# Sample.net
KiCad netlist of a schematic drawn in EAGLE
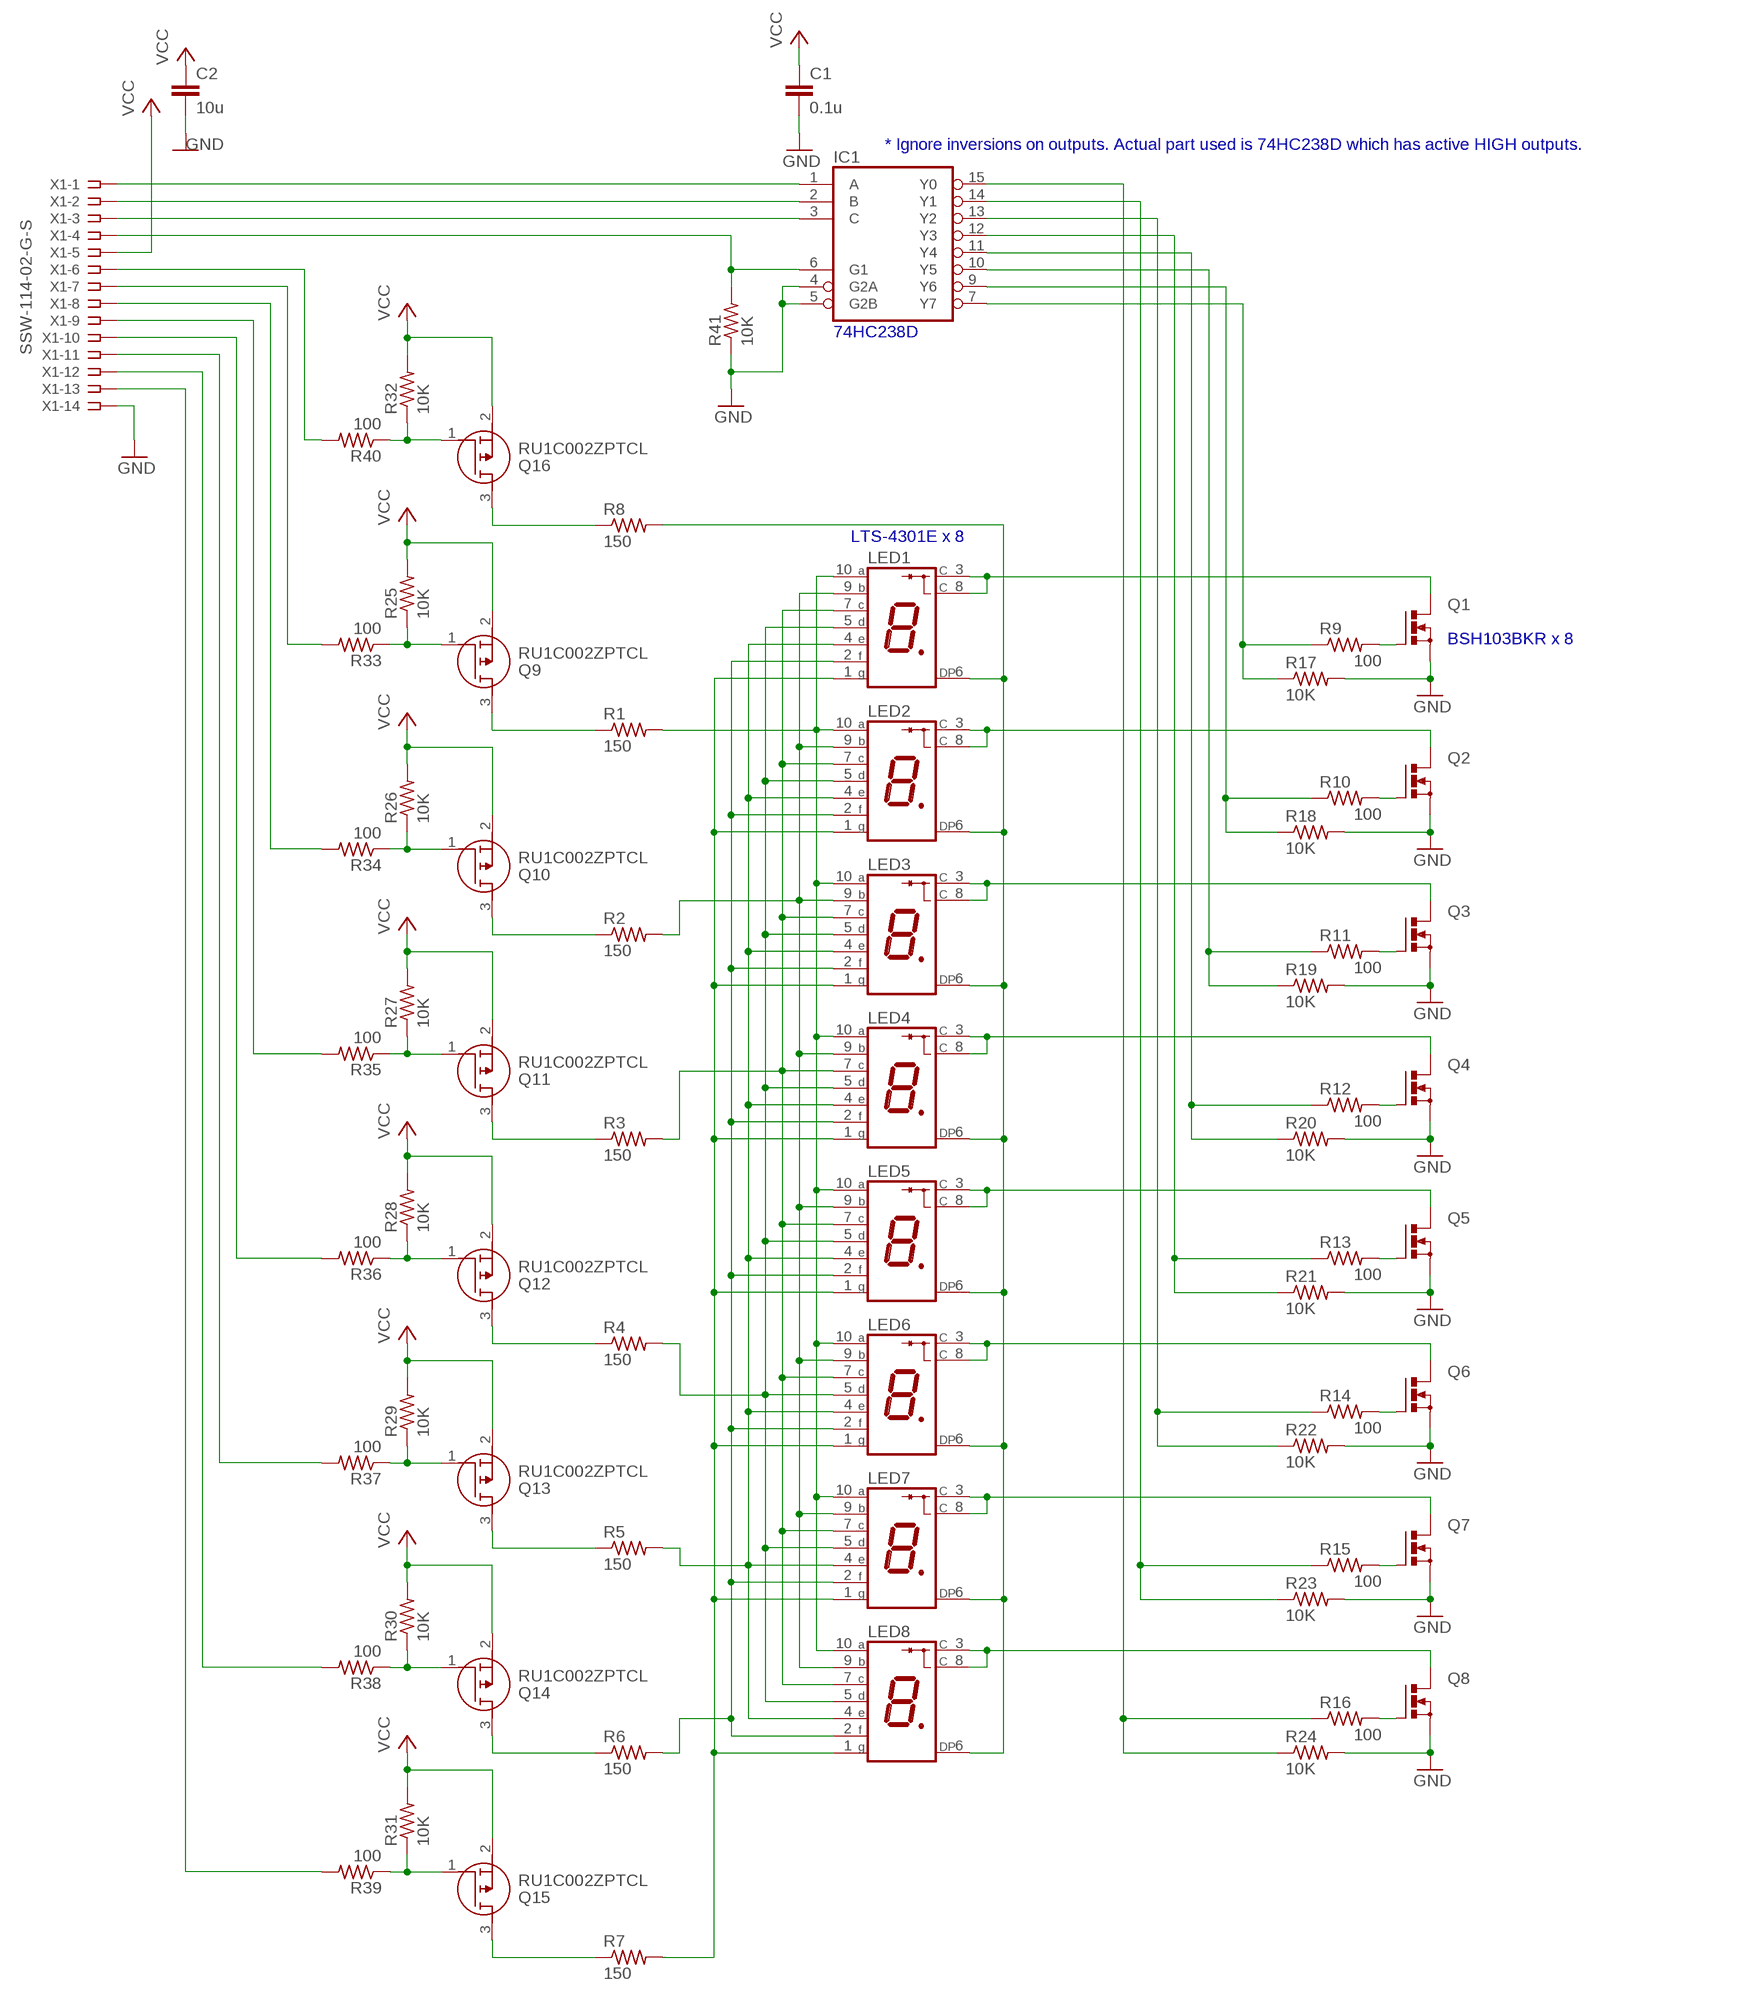
[diagram p0: schematic, sheet 1]

(export (version "E")
  (design (tool "Eeschema 10.0.6"))
  (components
    (comp (ref "C1")
      (value "0.1u")
      (footprint "eagle-import:C0805")
      (libsource (lib "eagle-import") (part "C-EUC0805"))
    )
    (comp (ref "C2")
      (value "10u")
      (footprint "eagle-import:C0805")
      (libsource (lib "eagle-import") (part "C-EUC0805"))
    )
    (comp (ref "IC1")
      (value "74S138D")
      (footprint "eagle-import:SO16")
      (libsource (lib "eagle-import") (part "74138DS"))
    )
    (comp (ref "LED1")
      (value "S4301B")
      (footprint "eagle-import:S4301B")
      (libsource (lib "eagle-import") (part "S4301B"))
    )
    (comp (ref "LED2")
      (value "S4301B")
      (footprint "eagle-import:S4301B")
      (libsource (lib "eagle-import") (part "S4301B"))
    )
    (comp (ref "LED3")
      (value "S4301B")
      (footprint "eagle-import:S4301B")
      (libsource (lib "eagle-import") (part "S4301B"))
    )
    (comp (ref "LED4")
      (value "S4301B")
      (footprint "eagle-import:S4301B")
      (libsource (lib "eagle-import") (part "S4301B"))
    )
    (comp (ref "LED5")
      (value "S4301B")
      (footprint "eagle-import:S4301B")
      (libsource (lib "eagle-import") (part "S4301B"))
    )
    (comp (ref "LED6")
      (value "S4301B")
      (footprint "eagle-import:S4301B")
      (libsource (lib "eagle-import") (part "S4301B"))
    )
    (comp (ref "LED7")
      (value "S4301B")
      (footprint "eagle-import:S4301B")
      (libsource (lib "eagle-import") (part "S4301B"))
    )
    (comp (ref "LED8")
      (value "S4301B")
      (footprint "eagle-import:S4301B")
      (libsource (lib "eagle-import") (part "S4301B"))
    )
    (comp (ref "Q1")
      (value "N-MOSFET-SO8")
      (footprint "eagle-import:SUPER-SOT3")
      (libsource (lib "eagle-import") (part "N-MOSFET-SO8"))
    )
    (comp (ref "Q2")
      (value "N-MOSFET-SO8")
      (footprint "eagle-import:SUPER-SOT3")
      (libsource (lib "eagle-import") (part "N-MOSFET-SO8"))
    )
    (comp (ref "Q3")
      (value "N-MOSFET-SO8")
      (footprint "eagle-import:SUPER-SOT3")
      (libsource (lib "eagle-import") (part "N-MOSFET-SO8"))
    )
    (comp (ref "Q4")
      (value "N-MOSFET-SO8")
      (footprint "eagle-import:SUPER-SOT3")
      (libsource (lib "eagle-import") (part "N-MOSFET-SO8"))
    )
    (comp (ref "Q5")
      (value "N-MOSFET-SO8")
      (footprint "eagle-import:SUPER-SOT3")
      (libsource (lib "eagle-import") (part "N-MOSFET-SO8"))
    )
    (comp (ref "Q6")
      (value "N-MOSFET-SO8")
      (footprint "eagle-import:SUPER-SOT3")
      (libsource (lib "eagle-import") (part "N-MOSFET-SO8"))
    )
    (comp (ref "Q7")
      (value "N-MOSFET-SO8")
      (footprint "eagle-import:SUPER-SOT3")
      (libsource (lib "eagle-import") (part "N-MOSFET-SO8"))
    )
    (comp (ref "Q8")
      (value "N-MOSFET-SO8")
      (footprint "eagle-import:SUPER-SOT3")
      (libsource (lib "eagle-import") (part "N-MOSFET-SO8"))
    )
    (comp (ref "Q9")
      (value "RU1C002ZPTCL")
      (footprint "eagle-import:SOTFL65P210X105-3N")
      (fields (field (name "MOUSER_PART_NUMBER") "755-RU1C002ZPTCL"))
      (libsource (lib "eagle-import") (part "RU1C002ZPTCL"))
    )
    (comp (ref "Q10")
      (value "RU1C002ZPTCL")
      (footprint "eagle-import:SOTFL65P210X105-3N")
      (fields (field (name "MOUSER_PART_NUMBER") "755-RU1C002ZPTCL"))
      (libsource (lib "eagle-import") (part "RU1C002ZPTCL"))
    )
    (comp (ref "Q11")
      (value "RU1C002ZPTCL")
      (footprint "eagle-import:SOTFL65P210X105-3N")
      (fields (field (name "MOUSER_PART_NUMBER") "755-RU1C002ZPTCL"))
      (libsource (lib "eagle-import") (part "RU1C002ZPTCL"))
    )
    (comp (ref "Q12")
      (value "RU1C002ZPTCL")
      (footprint "eagle-import:SOTFL65P210X105-3N")
      (fields (field (name "MOUSER_PART_NUMBER") "755-RU1C002ZPTCL"))
      (libsource (lib "eagle-import") (part "RU1C002ZPTCL"))
    )
    (comp (ref "Q13")
      (value "RU1C002ZPTCL")
      (footprint "eagle-import:SOTFL65P210X105-3N")
      (fields (field (name "MOUSER_PART_NUMBER") "755-RU1C002ZPTCL"))
      (libsource (lib "eagle-import") (part "RU1C002ZPTCL"))
    )
    (comp (ref "Q14")
      (value "RU1C002ZPTCL")
      (footprint "eagle-import:SOTFL65P210X105-3N")
      (fields (field (name "MOUSER_PART_NUMBER") "755-RU1C002ZPTCL"))
      (libsource (lib "eagle-import") (part "RU1C002ZPTCL"))
    )
    (comp (ref "Q15")
      (value "RU1C002ZPTCL")
      (footprint "eagle-import:SOTFL65P210X105-3N")
      (fields (field (name "MOUSER_PART_NUMBER") "755-RU1C002ZPTCL"))
      (libsource (lib "eagle-import") (part "RU1C002ZPTCL"))
    )
    (comp (ref "Q16")
      (value "RU1C002ZPTCL")
      (footprint "eagle-import:SOTFL65P210X105-3N")
      (fields (field (name "MOUSER_PART_NUMBER") "755-RU1C002ZPTCL"))
      (libsource (lib "eagle-import") (part "RU1C002ZPTCL"))
    )
    (comp (ref "R1")
      (value "150")
      (footprint "eagle-import:R0805")
      (libsource (lib "eagle-import") (part "R-US_R0805"))
    )
    (comp (ref "R2")
      (value "150")
      (footprint "eagle-import:R0805")
      (libsource (lib "eagle-import") (part "R-US_R0805"))
    )
    (comp (ref "R3")
      (value "150")
      (footprint "eagle-import:R0805")
      (libsource (lib "eagle-import") (part "R-US_R0805"))
    )
    (comp (ref "R4")
      (value "150")
      (footprint "eagle-import:R0805")
      (libsource (lib "eagle-import") (part "R-US_R0805"))
    )
    (comp (ref "R5")
      (value "150")
      (footprint "eagle-import:R0805")
      (libsource (lib "eagle-import") (part "R-US_R0805"))
    )
    (comp (ref "R6")
      (value "150")
      (footprint "eagle-import:R0805")
      (libsource (lib "eagle-import") (part "R-US_R0805"))
    )
    (comp (ref "R7")
      (value "150")
      (footprint "eagle-import:R0805")
      (libsource (lib "eagle-import") (part "R-US_R0805"))
    )
    (comp (ref "R8")
      (value "150")
      (footprint "eagle-import:R0805")
      (libsource (lib "eagle-import") (part "R-US_R0805"))
    )
    (comp (ref "R9")
      (value "100")
      (footprint "eagle-import:R0805")
      (libsource (lib "eagle-import") (part "R-US_R0805"))
    )
    (comp (ref "R10")
      (value "100")
      (footprint "eagle-import:R0805")
      (libsource (lib "eagle-import") (part "R-US_R0805"))
    )
    (comp (ref "R11")
      (value "100")
      (footprint "eagle-import:R0805")
      (libsource (lib "eagle-import") (part "R-US_R0805"))
    )
    (comp (ref "R12")
      (value "100")
      (footprint "eagle-import:R0805")
      (libsource (lib "eagle-import") (part "R-US_R0805"))
    )
    (comp (ref "R13")
      (value "100")
      (footprint "eagle-import:R0805")
      (libsource (lib "eagle-import") (part "R-US_R0805"))
    )
    (comp (ref "R14")
      (value "100")
      (footprint "eagle-import:R0805")
      (libsource (lib "eagle-import") (part "R-US_R0805"))
    )
    (comp (ref "R15")
      (value "100")
      (footprint "eagle-import:R0805")
      (libsource (lib "eagle-import") (part "R-US_R0805"))
    )
    (comp (ref "R16")
      (value "100")
      (footprint "eagle-import:R0805")
      (libsource (lib "eagle-import") (part "R-US_R0805"))
    )
    (comp (ref "R17")
      (value "10K")
      (footprint "eagle-import:R0805")
      (libsource (lib "eagle-import") (part "R-US_R0805"))
    )
    (comp (ref "R18")
      (value "10K")
      (footprint "eagle-import:R0805")
      (libsource (lib "eagle-import") (part "R-US_R0805"))
    )
    (comp (ref "R19")
      (value "10K")
      (footprint "eagle-import:R0805")
      (libsource (lib "eagle-import") (part "R-US_R0805"))
    )
    (comp (ref "R20")
      (value "10K")
      (footprint "eagle-import:R0805")
      (libsource (lib "eagle-import") (part "R-US_R0805"))
    )
    (comp (ref "R21")
      (value "10K")
      (footprint "eagle-import:R0805")
      (libsource (lib "eagle-import") (part "R-US_R0805"))
    )
    (comp (ref "R22")
      (value "10K")
      (footprint "eagle-import:R0805")
      (libsource (lib "eagle-import") (part "R-US_R0805"))
    )
    (comp (ref "R23")
      (value "10K")
      (footprint "eagle-import:R0805")
      (libsource (lib "eagle-import") (part "R-US_R0805"))
    )
    (comp (ref "R24")
      (value "10K")
      (footprint "eagle-import:R0805")
      (libsource (lib "eagle-import") (part "R-US_R0805"))
    )
    (comp (ref "R25")
      (value "10K")
      (footprint "eagle-import:R0805")
      (libsource (lib "eagle-import") (part "R-US_R0805"))
    )
    (comp (ref "R26")
      (value "10K")
      (footprint "eagle-import:R0805")
      (libsource (lib "eagle-import") (part "R-US_R0805"))
    )
    (comp (ref "R27")
      (value "10K")
      (footprint "eagle-import:R0805")
      (libsource (lib "eagle-import") (part "R-US_R0805"))
    )
    (comp (ref "R28")
      (value "10K")
      (footprint "eagle-import:R0805")
      (libsource (lib "eagle-import") (part "R-US_R0805"))
    )
    (comp (ref "R29")
      (value "10K")
      (footprint "eagle-import:R0805")
      (libsource (lib "eagle-import") (part "R-US_R0805"))
    )
    (comp (ref "R30")
      (value "10K")
      (footprint "eagle-import:R0805")
      (libsource (lib "eagle-import") (part "R-US_R0805"))
    )
    (comp (ref "R31")
      (value "10K")
      (footprint "eagle-import:R0805")
      (libsource (lib "eagle-import") (part "R-US_R0805"))
    )
    (comp (ref "R32")
      (value "10K")
      (footprint "eagle-import:R0805")
      (libsource (lib "eagle-import") (part "R-US_R0805"))
    )
    (comp (ref "R33")
      (value "100")
      (footprint "eagle-import:R0805")
      (libsource (lib "eagle-import") (part "R-US_R0805"))
    )
    (comp (ref "R34")
      (value "100")
      (footprint "eagle-import:R0805")
      (libsource (lib "eagle-import") (part "R-US_R0805"))
    )
    (comp (ref "R35")
      (value "100")
      (footprint "eagle-import:R0805")
      (libsource (lib "eagle-import") (part "R-US_R0805"))
    )
    (comp (ref "R36")
      (value "100")
      (footprint "eagle-import:R0805")
      (libsource (lib "eagle-import") (part "R-US_R0805"))
    )
    (comp (ref "R37")
      (value "100")
      (footprint "eagle-import:R0805")
      (libsource (lib "eagle-import") (part "R-US_R0805"))
    )
    (comp (ref "R38")
      (value "100")
      (footprint "eagle-import:R0805")
      (libsource (lib "eagle-import") (part "R-US_R0805"))
    )
    (comp (ref "R39")
      (value "100")
      (footprint "eagle-import:R0805")
      (libsource (lib "eagle-import") (part "R-US_R0805"))
    )
    (comp (ref "R40")
      (value "100")
      (footprint "eagle-import:R0805")
      (libsource (lib "eagle-import") (part "R-US_R0805"))
    )
    (comp (ref "R41")
      (value "10K")
      (footprint "eagle-import:R0805")
      (libsource (lib "eagle-import") (part "R-US_R0805"))
    )
    (comp (ref "X1")
      (value "SSW-114-02-G-S")
      (footprint "eagle-import:SSW-114-02-G-S")
      (fields (field (name "MF") "Samtec Inc."))
      (libsource (lib "eagle-import") (part "SSW-114-02-G-S"))
    )
  )
  (nets
    (net (code "1") (name "GND") (class "Default")
      (node (ref "C1") (pin "2") (pinfunction "2_2") (pintype "passive"))
      (node (ref "C2") (pin "2") (pinfunction "2_2") (pintype "passive"))
      (node (ref "IC1") (pin "4") (pinfunction "G2A_4") (pintype "input"))
      (node (ref "IC1") (pin "5") (pinfunction "G2B_5") (pintype "input"))
      (node (ref "Q1") (pin "2") (pinfunction "S_2") (pintype "passive"))
      (node (ref "Q2") (pin "2") (pinfunction "S_2") (pintype "passive"))
      (node (ref "Q3") (pin "2") (pinfunction "S_2") (pintype "passive"))
      (node (ref "Q4") (pin "2") (pinfunction "S_2") (pintype "passive"))
      (node (ref "Q5") (pin "2") (pinfunction "S_2") (pintype "passive"))
      (node (ref "Q6") (pin "2") (pinfunction "S_2") (pintype "passive"))
      (node (ref "Q7") (pin "2") (pinfunction "S_2") (pintype "passive"))
      (node (ref "Q8") (pin "2") (pinfunction "S_2") (pintype "passive"))
      (node (ref "R17") (pin "2") (pinfunction "2_2") (pintype "passive"))
      (node (ref "R18") (pin "2") (pinfunction "2_2") (pintype "passive"))
      (node (ref "R19") (pin "2") (pinfunction "2_2") (pintype "passive"))
      (node (ref "R20") (pin "2") (pinfunction "2_2") (pintype "passive"))
      (node (ref "R21") (pin "2") (pinfunction "2_2") (pintype "passive"))
      (node (ref "R22") (pin "2") (pinfunction "2_2") (pintype "passive"))
      (node (ref "R23") (pin "2") (pinfunction "2_2") (pintype "passive"))
      (node (ref "R24") (pin "2") (pinfunction "2_2") (pintype "passive"))
      (node (ref "R41") (pin "1") (pinfunction "1_1") (pintype "passive"))
      (node (ref "X1") (pin "14") (pinfunction "1_14") (pintype "passive"))
    )
    (net (code "2") (name "Net-(IC1A-A)") (class "Default")
      (node (ref "IC1") (pin "1") (pinfunction "A_1") (pintype "input"))
      (node (ref "X1") (pin "1") (pinfunction "1_1") (pintype "passive"))
    )
    (net (code "3") (name "Net-(IC1A-B)") (class "Default")
      (node (ref "IC1") (pin "2") (pinfunction "B_2") (pintype "input"))
      (node (ref "X1") (pin "2") (pinfunction "1_2") (pintype "passive"))
    )
    (net (code "4") (name "Net-(IC1A-C)") (class "Default")
      (node (ref "IC1") (pin "3") (pinfunction "C_3") (pintype "input"))
      (node (ref "X1") (pin "3") (pinfunction "1_3") (pintype "passive"))
    )
    (net (code "5") (name "Net-(IC1A-G1)") (class "Default")
      (node (ref "IC1") (pin "6") (pinfunction "G1_6") (pintype "input"))
      (node (ref "R41") (pin "2") (pinfunction "2_2") (pintype "passive"))
      (node (ref "X1") (pin "4") (pinfunction "1_4") (pintype "passive"))
    )
    (net (code "6") (name "Net-(IC1A-Y0)") (class "Default")
      (node (ref "IC1") (pin "15") (pinfunction "Y0_15") (pintype "output"))
      (node (ref "R16") (pin "1") (pinfunction "1_1") (pintype "passive"))
      (node (ref "R24") (pin "1") (pinfunction "1_1") (pintype "passive"))
    )
    (net (code "7") (name "Net-(IC1A-Y1)") (class "Default")
      (node (ref "IC1") (pin "14") (pinfunction "Y1_14") (pintype "output"))
      (node (ref "R15") (pin "1") (pinfunction "1_1") (pintype "passive"))
      (node (ref "R23") (pin "1") (pinfunction "1_1") (pintype "passive"))
    )
    (net (code "8") (name "Net-(IC1A-Y2)") (class "Default")
      (node (ref "IC1") (pin "13") (pinfunction "Y2_13") (pintype "output"))
      (node (ref "R14") (pin "1") (pinfunction "1_1") (pintype "passive"))
      (node (ref "R22") (pin "1") (pinfunction "1_1") (pintype "passive"))
    )
    (net (code "9") (name "Net-(IC1A-Y3)") (class "Default")
      (node (ref "IC1") (pin "12") (pinfunction "Y3_12") (pintype "output"))
      (node (ref "R13") (pin "1") (pinfunction "1_1") (pintype "passive"))
      (node (ref "R21") (pin "1") (pinfunction "1_1") (pintype "passive"))
    )
    (net (code "10") (name "Net-(IC1A-Y4)") (class "Default")
      (node (ref "IC1") (pin "11") (pinfunction "Y4_11") (pintype "output"))
      (node (ref "R12") (pin "1") (pinfunction "1_1") (pintype "passive"))
      (node (ref "R20") (pin "1") (pinfunction "1_1") (pintype "passive"))
    )
    (net (code "11") (name "Net-(IC1A-Y5)") (class "Default")
      (node (ref "IC1") (pin "10") (pinfunction "Y5_10") (pintype "output"))
      (node (ref "R11") (pin "1") (pinfunction "1_1") (pintype "passive"))
      (node (ref "R19") (pin "1") (pinfunction "1_1") (pintype "passive"))
    )
    (net (code "12") (name "Net-(IC1A-Y6)") (class "Default")
      (node (ref "IC1") (pin "9") (pinfunction "Y6_9") (pintype "output"))
      (node (ref "R10") (pin "1") (pinfunction "1_1") (pintype "passive"))
      (node (ref "R18") (pin "1") (pinfunction "1_1") (pintype "passive"))
    )
    (net (code "13") (name "Net-(IC1A-Y7)") (class "Default")
      (node (ref "IC1") (pin "7") (pinfunction "Y7_7") (pintype "output"))
      (node (ref "R17") (pin "1") (pinfunction "1_1") (pintype "passive"))
      (node (ref "R9") (pin "1") (pinfunction "1_1") (pintype "passive"))
    )
    (net (code "14") (name "Net-(LED1-A)") (class "Default")
      (node (ref "LED1") (pin "10") (pinfunction "A_10") (pintype "passive"))
      (node (ref "LED2") (pin "10") (pinfunction "A_10") (pintype "passive"))
      (node (ref "LED3") (pin "10") (pinfunction "A_10") (pintype "passive"))
      (node (ref "LED4") (pin "10") (pinfunction "A_10") (pintype "passive"))
      (node (ref "LED5") (pin "10") (pinfunction "A_10") (pintype "passive"))
      (node (ref "LED6") (pin "10") (pinfunction "A_10") (pintype "passive"))
      (node (ref "LED7") (pin "10") (pinfunction "A_10") (pintype "passive"))
      (node (ref "LED8") (pin "10") (pinfunction "A_10") (pintype "passive"))
      (node (ref "R1") (pin "2") (pinfunction "2_2") (pintype "passive"))
    )
    (net (code "15") (name "Net-(LED1-B)") (class "Default")
      (node (ref "LED1") (pin "9") (pinfunction "B_9") (pintype "passive"))
      (node (ref "LED2") (pin "9") (pinfunction "B_9") (pintype "passive"))
      (node (ref "LED3") (pin "9") (pinfunction "B_9") (pintype "passive"))
      (node (ref "LED4") (pin "9") (pinfunction "B_9") (pintype "passive"))
      (node (ref "LED5") (pin "9") (pinfunction "B_9") (pintype "passive"))
      (node (ref "LED6") (pin "9") (pinfunction "B_9") (pintype "passive"))
      (node (ref "LED7") (pin "9") (pinfunction "B_9") (pintype "passive"))
      (node (ref "LED8") (pin "9") (pinfunction "B_9") (pintype "passive"))
      (node (ref "R2") (pin "2") (pinfunction "2_2") (pintype "passive"))
    )
    (net (code "16") (name "Net-(LED1-C-Pad7)") (class "Default")
      (node (ref "LED1") (pin "7") (pinfunction "C_7") (pintype "passive"))
      (node (ref "LED2") (pin "7") (pinfunction "C_7") (pintype "passive"))
      (node (ref "LED3") (pin "7") (pinfunction "C_7") (pintype "passive"))
      (node (ref "LED4") (pin "7") (pinfunction "C_7") (pintype "passive"))
      (node (ref "LED5") (pin "7") (pinfunction "C_7") (pintype "passive"))
      (node (ref "LED6") (pin "7") (pinfunction "C_7") (pintype "passive"))
      (node (ref "LED7") (pin "7") (pinfunction "C_7") (pintype "passive"))
      (node (ref "LED8") (pin "7") (pinfunction "C_7") (pintype "passive"))
      (node (ref "R3") (pin "2") (pinfunction "2_2") (pintype "passive"))
    )
    (net (code "17") (name "Net-(LED1-D)") (class "Default")
      (node (ref "LED1") (pin "5") (pinfunction "D_5") (pintype "passive"))
      (node (ref "LED2") (pin "5") (pinfunction "D_5") (pintype "passive"))
      (node (ref "LED3") (pin "5") (pinfunction "D_5") (pintype "passive"))
      (node (ref "LED4") (pin "5") (pinfunction "D_5") (pintype "passive"))
      (node (ref "LED5") (pin "5") (pinfunction "D_5") (pintype "passive"))
      (node (ref "LED6") (pin "5") (pinfunction "D_5") (pintype "passive"))
      (node (ref "LED7") (pin "5") (pinfunction "D_5") (pintype "passive"))
      (node (ref "LED8") (pin "5") (pinfunction "D_5") (pintype "passive"))
      (node (ref "R4") (pin "2") (pinfunction "2_2") (pintype "passive"))
    )
    (net (code "18") (name "Net-(LED1-DP)") (class "Default")
      (node (ref "LED1") (pin "6") (pinfunction "DP_6") (pintype "passive"))
      (node (ref "LED2") (pin "6") (pinfunction "DP_6") (pintype "passive"))
      (node (ref "LED3") (pin "6") (pinfunction "DP_6") (pintype "passive"))
      (node (ref "LED4") (pin "6") (pinfunction "DP_6") (pintype "passive"))
      (node (ref "LED5") (pin "6") (pinfunction "DP_6") (pintype "passive"))
      (node (ref "LED6") (pin "6") (pinfunction "DP_6") (pintype "passive"))
      (node (ref "LED7") (pin "6") (pinfunction "DP_6") (pintype "passive"))
      (node (ref "LED8") (pin "6") (pinfunction "DP_6") (pintype "passive"))
      (node (ref "R8") (pin "2") (pinfunction "2_2") (pintype "passive"))
    )
    (net (code "19") (name "Net-(LED1-E)") (class "Default")
      (node (ref "LED1") (pin "4") (pinfunction "E_4") (pintype "passive"))
      (node (ref "LED2") (pin "4") (pinfunction "E_4") (pintype "passive"))
      (node (ref "LED3") (pin "4") (pinfunction "E_4") (pintype "passive"))
      (node (ref "LED4") (pin "4") (pinfunction "E_4") (pintype "passive"))
      (node (ref "LED5") (pin "4") (pinfunction "E_4") (pintype "passive"))
      (node (ref "LED6") (pin "4") (pinfunction "E_4") (pintype "passive"))
      (node (ref "LED7") (pin "4") (pinfunction "E_4") (pintype "passive"))
      (node (ref "LED8") (pin "4") (pinfunction "E_4") (pintype "passive"))
      (node (ref "R5") (pin "2") (pinfunction "2_2") (pintype "passive"))
    )
    (net (code "20") (name "Net-(LED1-F)") (class "Default")
      (node (ref "LED1") (pin "2") (pinfunction "F_2") (pintype "passive"))
      (node (ref "LED2") (pin "2") (pinfunction "F_2") (pintype "passive"))
      (node (ref "LED3") (pin "2") (pinfunction "F_2") (pintype "passive"))
      (node (ref "LED4") (pin "2") (pinfunction "F_2") (pintype "passive"))
      (node (ref "LED5") (pin "2") (pinfunction "F_2") (pintype "passive"))
      (node (ref "LED6") (pin "2") (pinfunction "F_2") (pintype "passive"))
      (node (ref "LED7") (pin "2") (pinfunction "F_2") (pintype "passive"))
      (node (ref "LED8") (pin "2") (pinfunction "F_2") (pintype "passive"))
      (node (ref "R6") (pin "2") (pinfunction "2_2") (pintype "passive"))
    )
    (net (code "21") (name "Net-(LED1-G)") (class "Default")
      (node (ref "LED1") (pin "1") (pinfunction "G_1") (pintype "passive"))
      (node (ref "LED2") (pin "1") (pinfunction "G_1") (pintype "passive"))
      (node (ref "LED3") (pin "1") (pinfunction "G_1") (pintype "passive"))
      (node (ref "LED4") (pin "1") (pinfunction "G_1") (pintype "passive"))
      (node (ref "LED5") (pin "1") (pinfunction "G_1") (pintype "passive"))
      (node (ref "LED6") (pin "1") (pinfunction "G_1") (pintype "passive"))
      (node (ref "LED7") (pin "1") (pinfunction "G_1") (pintype "passive"))
      (node (ref "LED8") (pin "1") (pinfunction "G_1") (pintype "passive"))
      (node (ref "R7") (pin "2") (pinfunction "2_2") (pintype "passive"))
    )
    (net (code "22") (name "Net-(Q1-D)") (class "Default")
      (node (ref "LED1") (pin "3") (pinfunction "C_3") (pintype "passive"))
      (node (ref "LED1") (pin "8") (pinfunction "C_8") (pintype "passive"))
      (node (ref "Q1") (pin "3") (pinfunction "D_3") (pintype "passive"))
    )
    (net (code "23") (name "Net-(Q1-G)") (class "Default")
      (node (ref "Q1") (pin "1") (pinfunction "G_1") (pintype "passive"))
      (node (ref "R9") (pin "2") (pinfunction "2_2") (pintype "passive"))
    )
    (net (code "24") (name "Net-(Q2-D)") (class "Default")
      (node (ref "LED2") (pin "3") (pinfunction "C_3") (pintype "passive"))
      (node (ref "LED2") (pin "8") (pinfunction "C_8") (pintype "passive"))
      (node (ref "Q2") (pin "3") (pinfunction "D_3") (pintype "passive"))
    )
    (net (code "25") (name "Net-(Q2-G)") (class "Default")
      (node (ref "Q2") (pin "1") (pinfunction "G_1") (pintype "passive"))
      (node (ref "R10") (pin "2") (pinfunction "2_2") (pintype "passive"))
    )
    (net (code "26") (name "Net-(Q3-D)") (class "Default")
      (node (ref "LED3") (pin "3") (pinfunction "C_3") (pintype "passive"))
      (node (ref "LED3") (pin "8") (pinfunction "C_8") (pintype "passive"))
      (node (ref "Q3") (pin "3") (pinfunction "D_3") (pintype "passive"))
    )
    (net (code "27") (name "Net-(Q3-G)") (class "Default")
      (node (ref "Q3") (pin "1") (pinfunction "G_1") (pintype "passive"))
      (node (ref "R11") (pin "2") (pinfunction "2_2") (pintype "passive"))
    )
    (net (code "28") (name "Net-(Q4-D)") (class "Default")
      (node (ref "LED4") (pin "3") (pinfunction "C_3") (pintype "passive"))
      (node (ref "LED4") (pin "8") (pinfunction "C_8") (pintype "passive"))
      (node (ref "Q4") (pin "3") (pinfunction "D_3") (pintype "passive"))
    )
    (net (code "29") (name "Net-(Q4-G)") (class "Default")
      (node (ref "Q4") (pin "1") (pinfunction "G_1") (pintype "passive"))
      (node (ref "R12") (pin "2") (pinfunction "2_2") (pintype "passive"))
    )
    (net (code "30") (name "Net-(Q5-D)") (class "Default")
      (node (ref "LED5") (pin "3") (pinfunction "C_3") (pintype "passive"))
      (node (ref "LED5") (pin "8") (pinfunction "C_8") (pintype "passive"))
      (node (ref "Q5") (pin "3") (pinfunction "D_3") (pintype "passive"))
    )
    (net (code "31") (name "Net-(Q5-G)") (class "Default")
      (node (ref "Q5") (pin "1") (pinfunction "G_1") (pintype "passive"))
      (node (ref "R13") (pin "2") (pinfunction "2_2") (pintype "passive"))
    )
    (net (code "32") (name "Net-(Q6-D)") (class "Default")
      (node (ref "LED6") (pin "3") (pinfunction "C_3") (pintype "passive"))
      (node (ref "LED6") (pin "8") (pinfunction "C_8") (pintype "passive"))
      (node (ref "Q6") (pin "3") (pinfunction "D_3") (pintype "passive"))
    )
    (net (code "33") (name "Net-(Q6-G)") (class "Default")
      (node (ref "Q6") (pin "1") (pinfunction "G_1") (pintype "passive"))
      (node (ref "R14") (pin "2") (pinfunction "2_2") (pintype "passive"))
    )
    (net (code "34") (name "Net-(Q7-D)") (class "Default")
      (node (ref "LED7") (pin "3") (pinfunction "C_3") (pintype "passive"))
      (node (ref "LED7") (pin "8") (pinfunction "C_8") (pintype "passive"))
      (node (ref "Q7") (pin "3") (pinfunction "D_3") (pintype "passive"))
    )
    (net (code "35") (name "Net-(Q7-G)") (class "Default")
      (node (ref "Q7") (pin "1") (pinfunction "G_1") (pintype "passive"))
      (node (ref "R15") (pin "2") (pinfunction "2_2") (pintype "passive"))
    )
    (net (code "36") (name "Net-(Q8-D)") (class "Default")
      (node (ref "LED8") (pin "3") (pinfunction "C_3") (pintype "passive"))
      (node (ref "LED8") (pin "8") (pinfunction "C_8") (pintype "passive"))
      (node (ref "Q8") (pin "3") (pinfunction "D_3") (pintype "passive"))
    )
    (net (code "37") (name "Net-(Q8-G)") (class "Default")
      (node (ref "Q8") (pin "1") (pinfunction "G_1") (pintype "passive"))
      (node (ref "R16") (pin "2") (pinfunction "2_2") (pintype "passive"))
    )
    (net (code "38") (name "Net-(Q9-D)") (class "Default")
      (node (ref "Q9") (pin "3") (pinfunction "D_3") (pintype "bidirectional"))
      (node (ref "R1") (pin "1") (pinfunction "1_1") (pintype "passive"))
    )
    (net (code "39") (name "Net-(Q9-G)") (class "Default")
      (node (ref "Q9") (pin "1") (pinfunction "G_1") (pintype "bidirectional"))
      (node (ref "R25") (pin "1") (pinfunction "1_1") (pintype "passive"))
      (node (ref "R33") (pin "1") (pinfunction "1_1") (pintype "passive"))
    )
    (net (code "40") (name "Net-(Q10-D)") (class "Default")
      (node (ref "Q10") (pin "3") (pinfunction "D_3") (pintype "bidirectional"))
      (node (ref "R2") (pin "1") (pinfunction "1_1") (pintype "passive"))
    )
    (net (code "41") (name "Net-(Q10-G)") (class "Default")
      (node (ref "Q10") (pin "1") (pinfunction "G_1") (pintype "bidirectional"))
      (node (ref "R26") (pin "1") (pinfunction "1_1") (pintype "passive"))
      (node (ref "R34") (pin "1") (pinfunction "1_1") (pintype "passive"))
    )
    (net (code "42") (name "Net-(Q11-D)") (class "Default")
      (node (ref "Q11") (pin "3") (pinfunction "D_3") (pintype "bidirectional"))
      (node (ref "R3") (pin "1") (pinfunction "1_1") (pintype "passive"))
    )
    (net (code "43") (name "Net-(Q11-G)") (class "Default")
      (node (ref "Q11") (pin "1") (pinfunction "G_1") (pintype "bidirectional"))
      (node (ref "R27") (pin "1") (pinfunction "1_1") (pintype "passive"))
      (node (ref "R35") (pin "1") (pinfunction "1_1") (pintype "passive"))
    )
    (net (code "44") (name "Net-(Q12-D)") (class "Default")
      (node (ref "Q12") (pin "3") (pinfunction "D_3") (pintype "bidirectional"))
      (node (ref "R4") (pin "1") (pinfunction "1_1") (pintype "passive"))
    )
    (net (code "45") (name "Net-(Q12-G)") (class "Default")
      (node (ref "Q12") (pin "1") (pinfunction "G_1") (pintype "bidirectional"))
      (node (ref "R28") (pin "1") (pinfunction "1_1") (pintype "passive"))
      (node (ref "R36") (pin "1") (pinfunction "1_1") (pintype "passive"))
    )
    (net (code "46") (name "Net-(Q13-D)") (class "Default")
      (node (ref "Q13") (pin "3") (pinfunction "D_3") (pintype "bidirectional"))
      (node (ref "R5") (pin "1") (pinfunction "1_1") (pintype "passive"))
    )
    (net (code "47") (name "Net-(Q13-G)") (class "Default")
      (node (ref "Q13") (pin "1") (pinfunction "G_1") (pintype "bidirectional"))
      (node (ref "R29") (pin "1") (pinfunction "1_1") (pintype "passive"))
      (node (ref "R37") (pin "1") (pinfunction "1_1") (pintype "passive"))
    )
    (net (code "48") (name "Net-(Q14-D)") (class "Default")
      (node (ref "Q14") (pin "3") (pinfunction "D_3") (pintype "bidirectional"))
      (node (ref "R6") (pin "1") (pinfunction "1_1") (pintype "passive"))
    )
    (net (code "49") (name "Net-(Q14-G)") (class "Default")
      (node (ref "Q14") (pin "1") (pinfunction "G_1") (pintype "bidirectional"))
      (node (ref "R30") (pin "1") (pinfunction "1_1") (pintype "passive"))
      (node (ref "R38") (pin "1") (pinfunction "1_1") (pintype "passive"))
    )
    (net (code "50") (name "Net-(Q15-D)") (class "Default")
      (node (ref "Q15") (pin "3") (pinfunction "D_3") (pintype "bidirectional"))
      (node (ref "R7") (pin "1") (pinfunction "1_1") (pintype "passive"))
    )
    (net (code "51") (name "Net-(Q15-G)") (class "Default")
      (node (ref "Q15") (pin "1") (pinfunction "G_1") (pintype "bidirectional"))
      (node (ref "R31") (pin "1") (pinfunction "1_1") (pintype "passive"))
      (node (ref "R39") (pin "1") (pinfunction "1_1") (pintype "passive"))
    )
    (net (code "52") (name "Net-(Q16-D)") (class "Default")
      (node (ref "Q16") (pin "3") (pinfunction "D_3") (pintype "bidirectional"))
      (node (ref "R8") (pin "1") (pinfunction "1_1") (pintype "passive"))
    )
    (net (code "53") (name "Net-(Q16-G)") (class "Default")
      (node (ref "Q16") (pin "1") (pinfunction "G_1") (pintype "bidirectional"))
      (node (ref "R32") (pin "1") (pinfunction "1_1") (pintype "passive"))
      (node (ref "R40") (pin "1") (pinfunction "1_1") (pintype "passive"))
    )
    (net (code "54") (name "Net-(X1B-1)") (class "Default")
      (node (ref "R36") (pin "2") (pinfunction "2_2") (pintype "passive"))
      (node (ref "X1") (pin "10") (pinfunction "1_10") (pintype "passive"))
    )
    (net (code "55") (name "Net-(X1C-1)") (class "Default")
      (node (ref "R37") (pin "2") (pinfunction "2_2") (pintype "passive"))
      (node (ref "X1") (pin "11") (pinfunction "1_11") (pintype "passive"))
    )
    (net (code "56") (name "Net-(X1D-1)") (class "Default")
      (node (ref "R38") (pin "2") (pinfunction "2_2") (pintype "passive"))
      (node (ref "X1") (pin "12") (pinfunction "1_12") (pintype "passive"))
    )
    (net (code "57") (name "Net-(X1E-1)") (class "Default")
      (node (ref "R39") (pin "2") (pinfunction "2_2") (pintype "passive"))
      (node (ref "X1") (pin "13") (pinfunction "1_13") (pintype "passive"))
    )
    (net (code "58") (name "Net-(X1K-1)") (class "Default")
      (node (ref "R40") (pin "2") (pinfunction "2_2") (pintype "passive"))
      (node (ref "X1") (pin "6") (pinfunction "1_6") (pintype "passive"))
    )
    (net (code "59") (name "Net-(X1L-1)") (class "Default")
      (node (ref "R33") (pin "2") (pinfunction "2_2") (pintype "passive"))
      (node (ref "X1") (pin "7") (pinfunction "1_7") (pintype "passive"))
    )
    (net (code "60") (name "Net-(X1M-1)") (class "Default")
      (node (ref "R34") (pin "2") (pinfunction "2_2") (pintype "passive"))
      (node (ref "X1") (pin "8") (pinfunction "1_8") (pintype "passive"))
    )
    (net (code "61") (name "Net-(X1N-1)") (class "Default")
      (node (ref "R35") (pin "2") (pinfunction "2_2") (pintype "passive"))
      (node (ref "X1") (pin "9") (pinfunction "1_9") (pintype "passive"))
    )
    (net (code "62") (name "VCC") (class "Default")
      (node (ref "C1") (pin "1") (pinfunction "1_1") (pintype "passive"))
      (node (ref "C2") (pin "1") (pinfunction "1_1") (pintype "passive"))
      (node (ref "Q10") (pin "2") (pinfunction "S_2") (pintype "bidirectional"))
      (node (ref "Q11") (pin "2") (pinfunction "S_2") (pintype "bidirectional"))
      (node (ref "Q12") (pin "2") (pinfunction "S_2") (pintype "bidirectional"))
      (node (ref "Q13") (pin "2") (pinfunction "S_2") (pintype "bidirectional"))
      (node (ref "Q14") (pin "2") (pinfunction "S_2") (pintype "bidirectional"))
      (node (ref "Q15") (pin "2") (pinfunction "S_2") (pintype "bidirectional"))
      (node (ref "Q16") (pin "2") (pinfunction "S_2") (pintype "bidirectional"))
      (node (ref "Q9") (pin "2") (pinfunction "S_2") (pintype "bidirectional"))
      (node (ref "R25") (pin "2") (pinfunction "2_2") (pintype "passive"))
      (node (ref "R26") (pin "2") (pinfunction "2_2") (pintype "passive"))
      (node (ref "R27") (pin "2") (pinfunction "2_2") (pintype "passive"))
      (node (ref "R28") (pin "2") (pinfunction "2_2") (pintype "passive"))
      (node (ref "R29") (pin "2") (pinfunction "2_2") (pintype "passive"))
      (node (ref "R30") (pin "2") (pinfunction "2_2") (pintype "passive"))
      (node (ref "R31") (pin "2") (pinfunction "2_2") (pintype "passive"))
      (node (ref "R32") (pin "2") (pinfunction "2_2") (pintype "passive"))
      (node (ref "X1") (pin "5") (pinfunction "1_5") (pintype "passive"))
    )
  )
)
